# integratedBertha.net
KiCad netlist of a schematic drawn in EAGLE
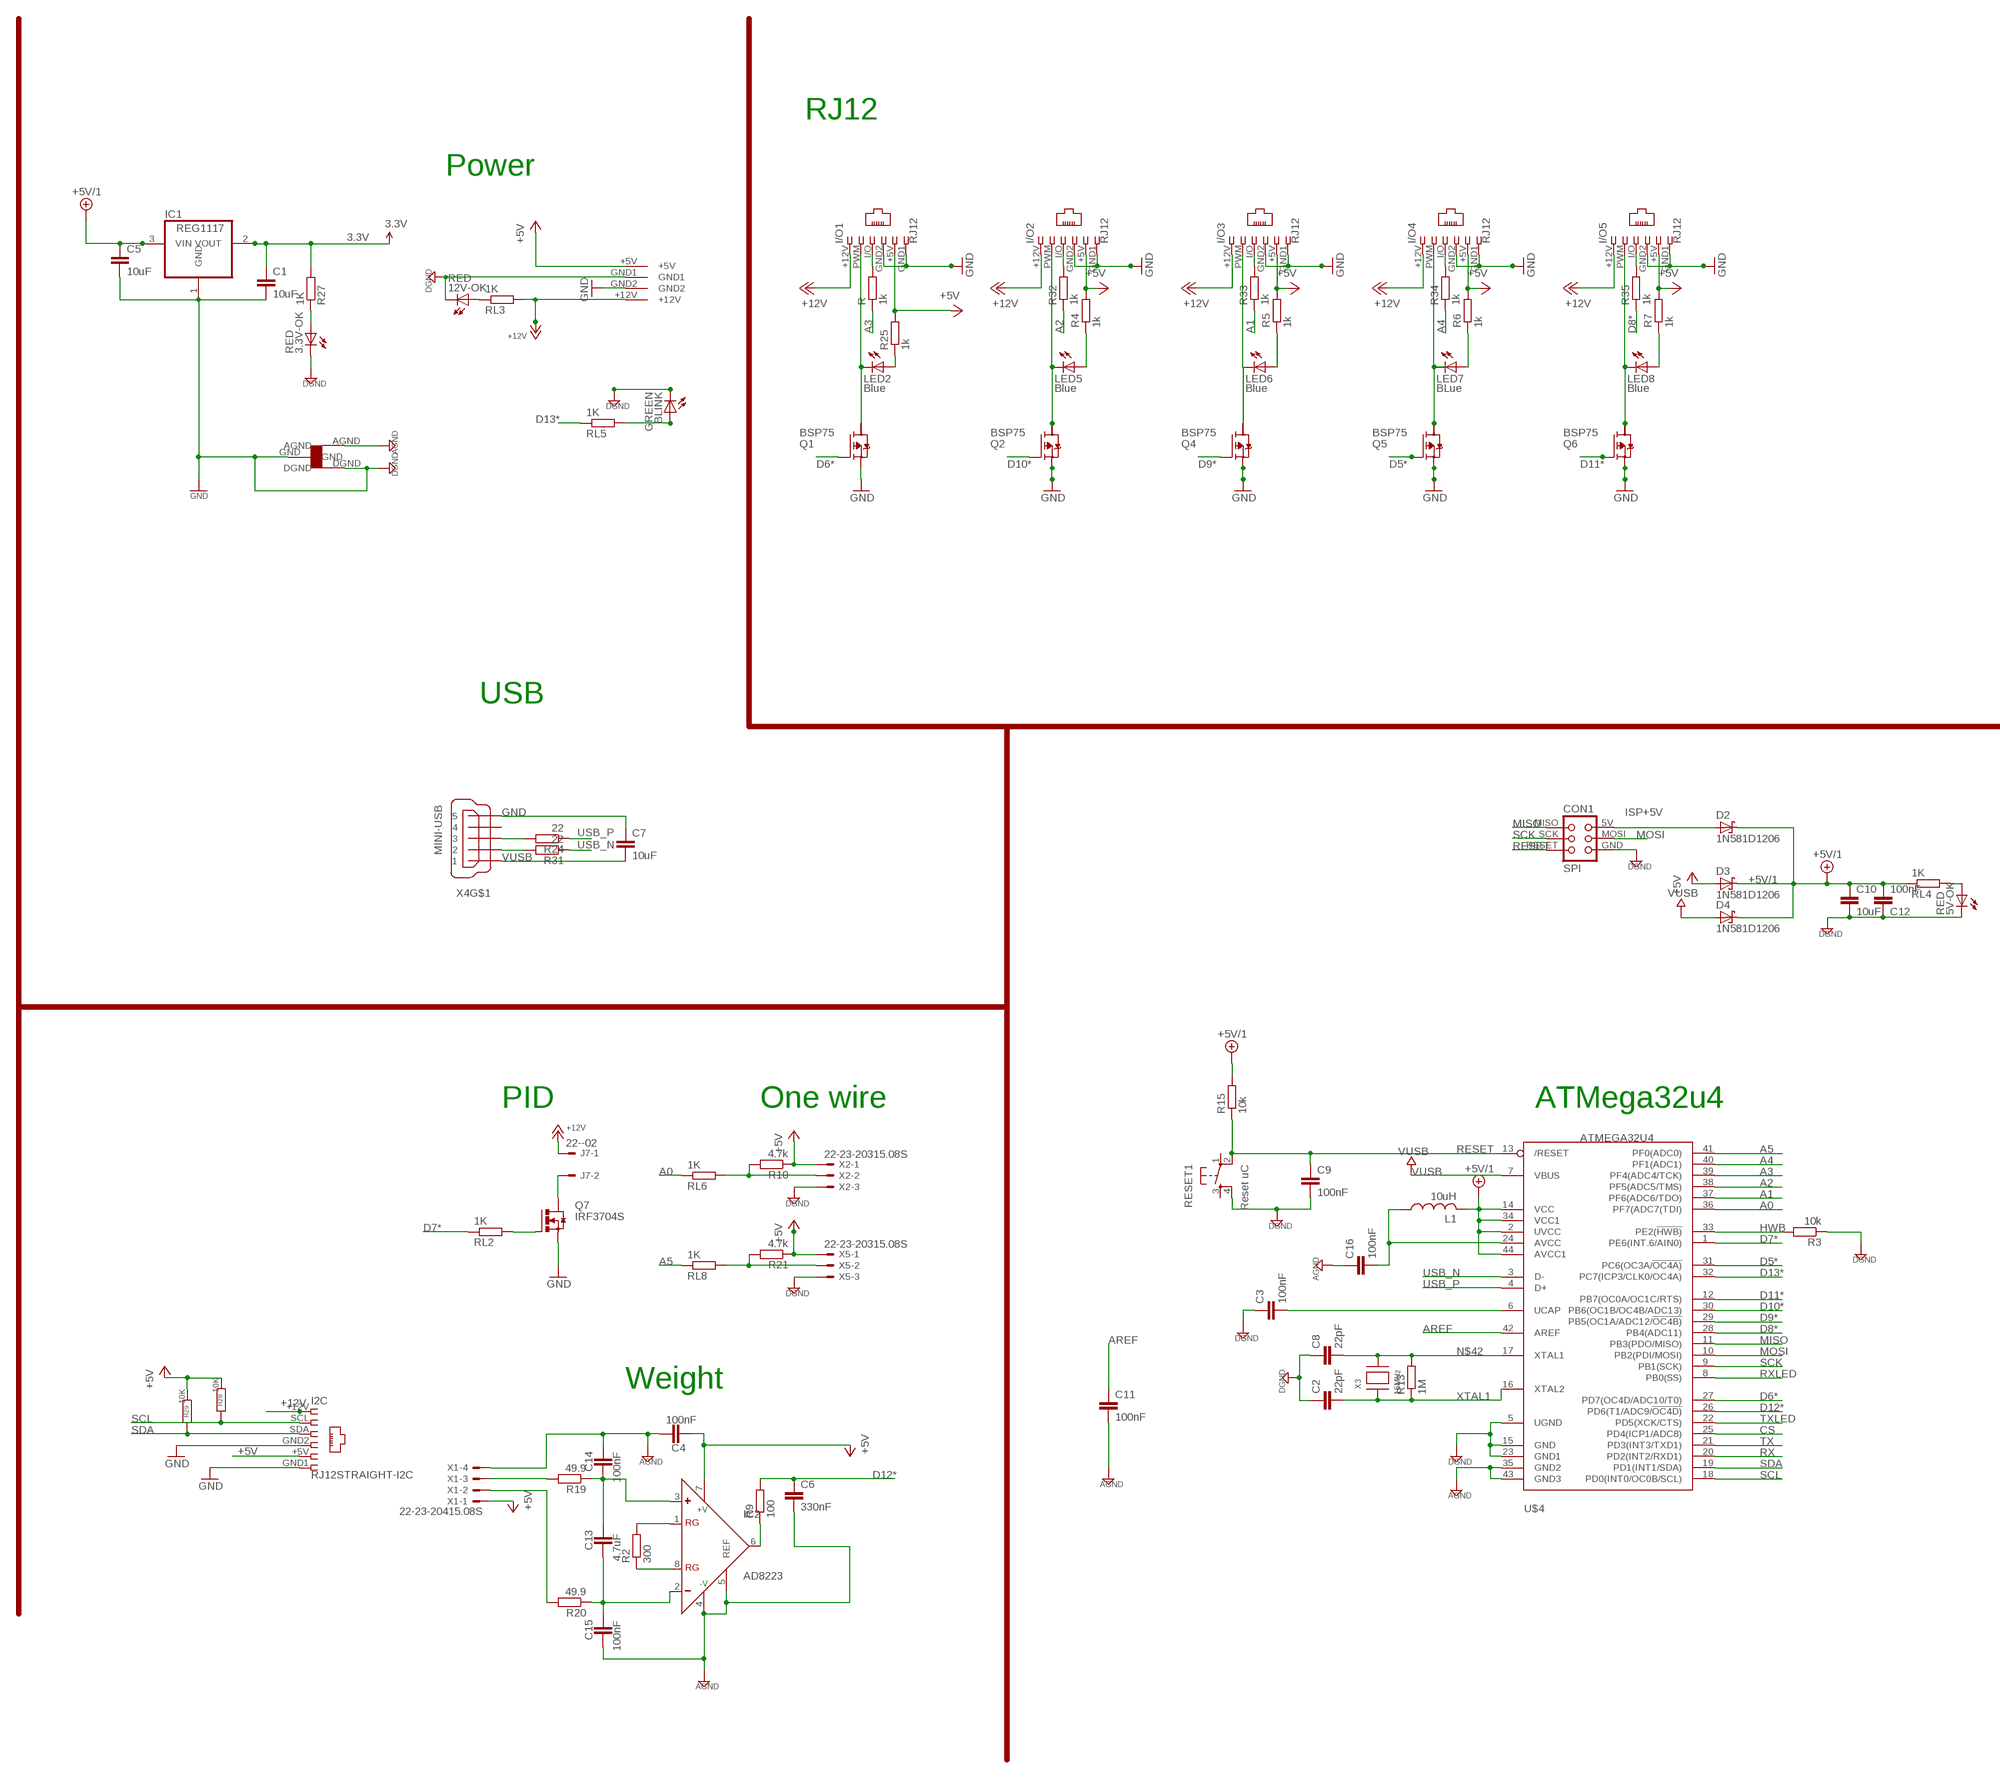
[diagram p0: schematic, sheet 1, part 1 of 2]
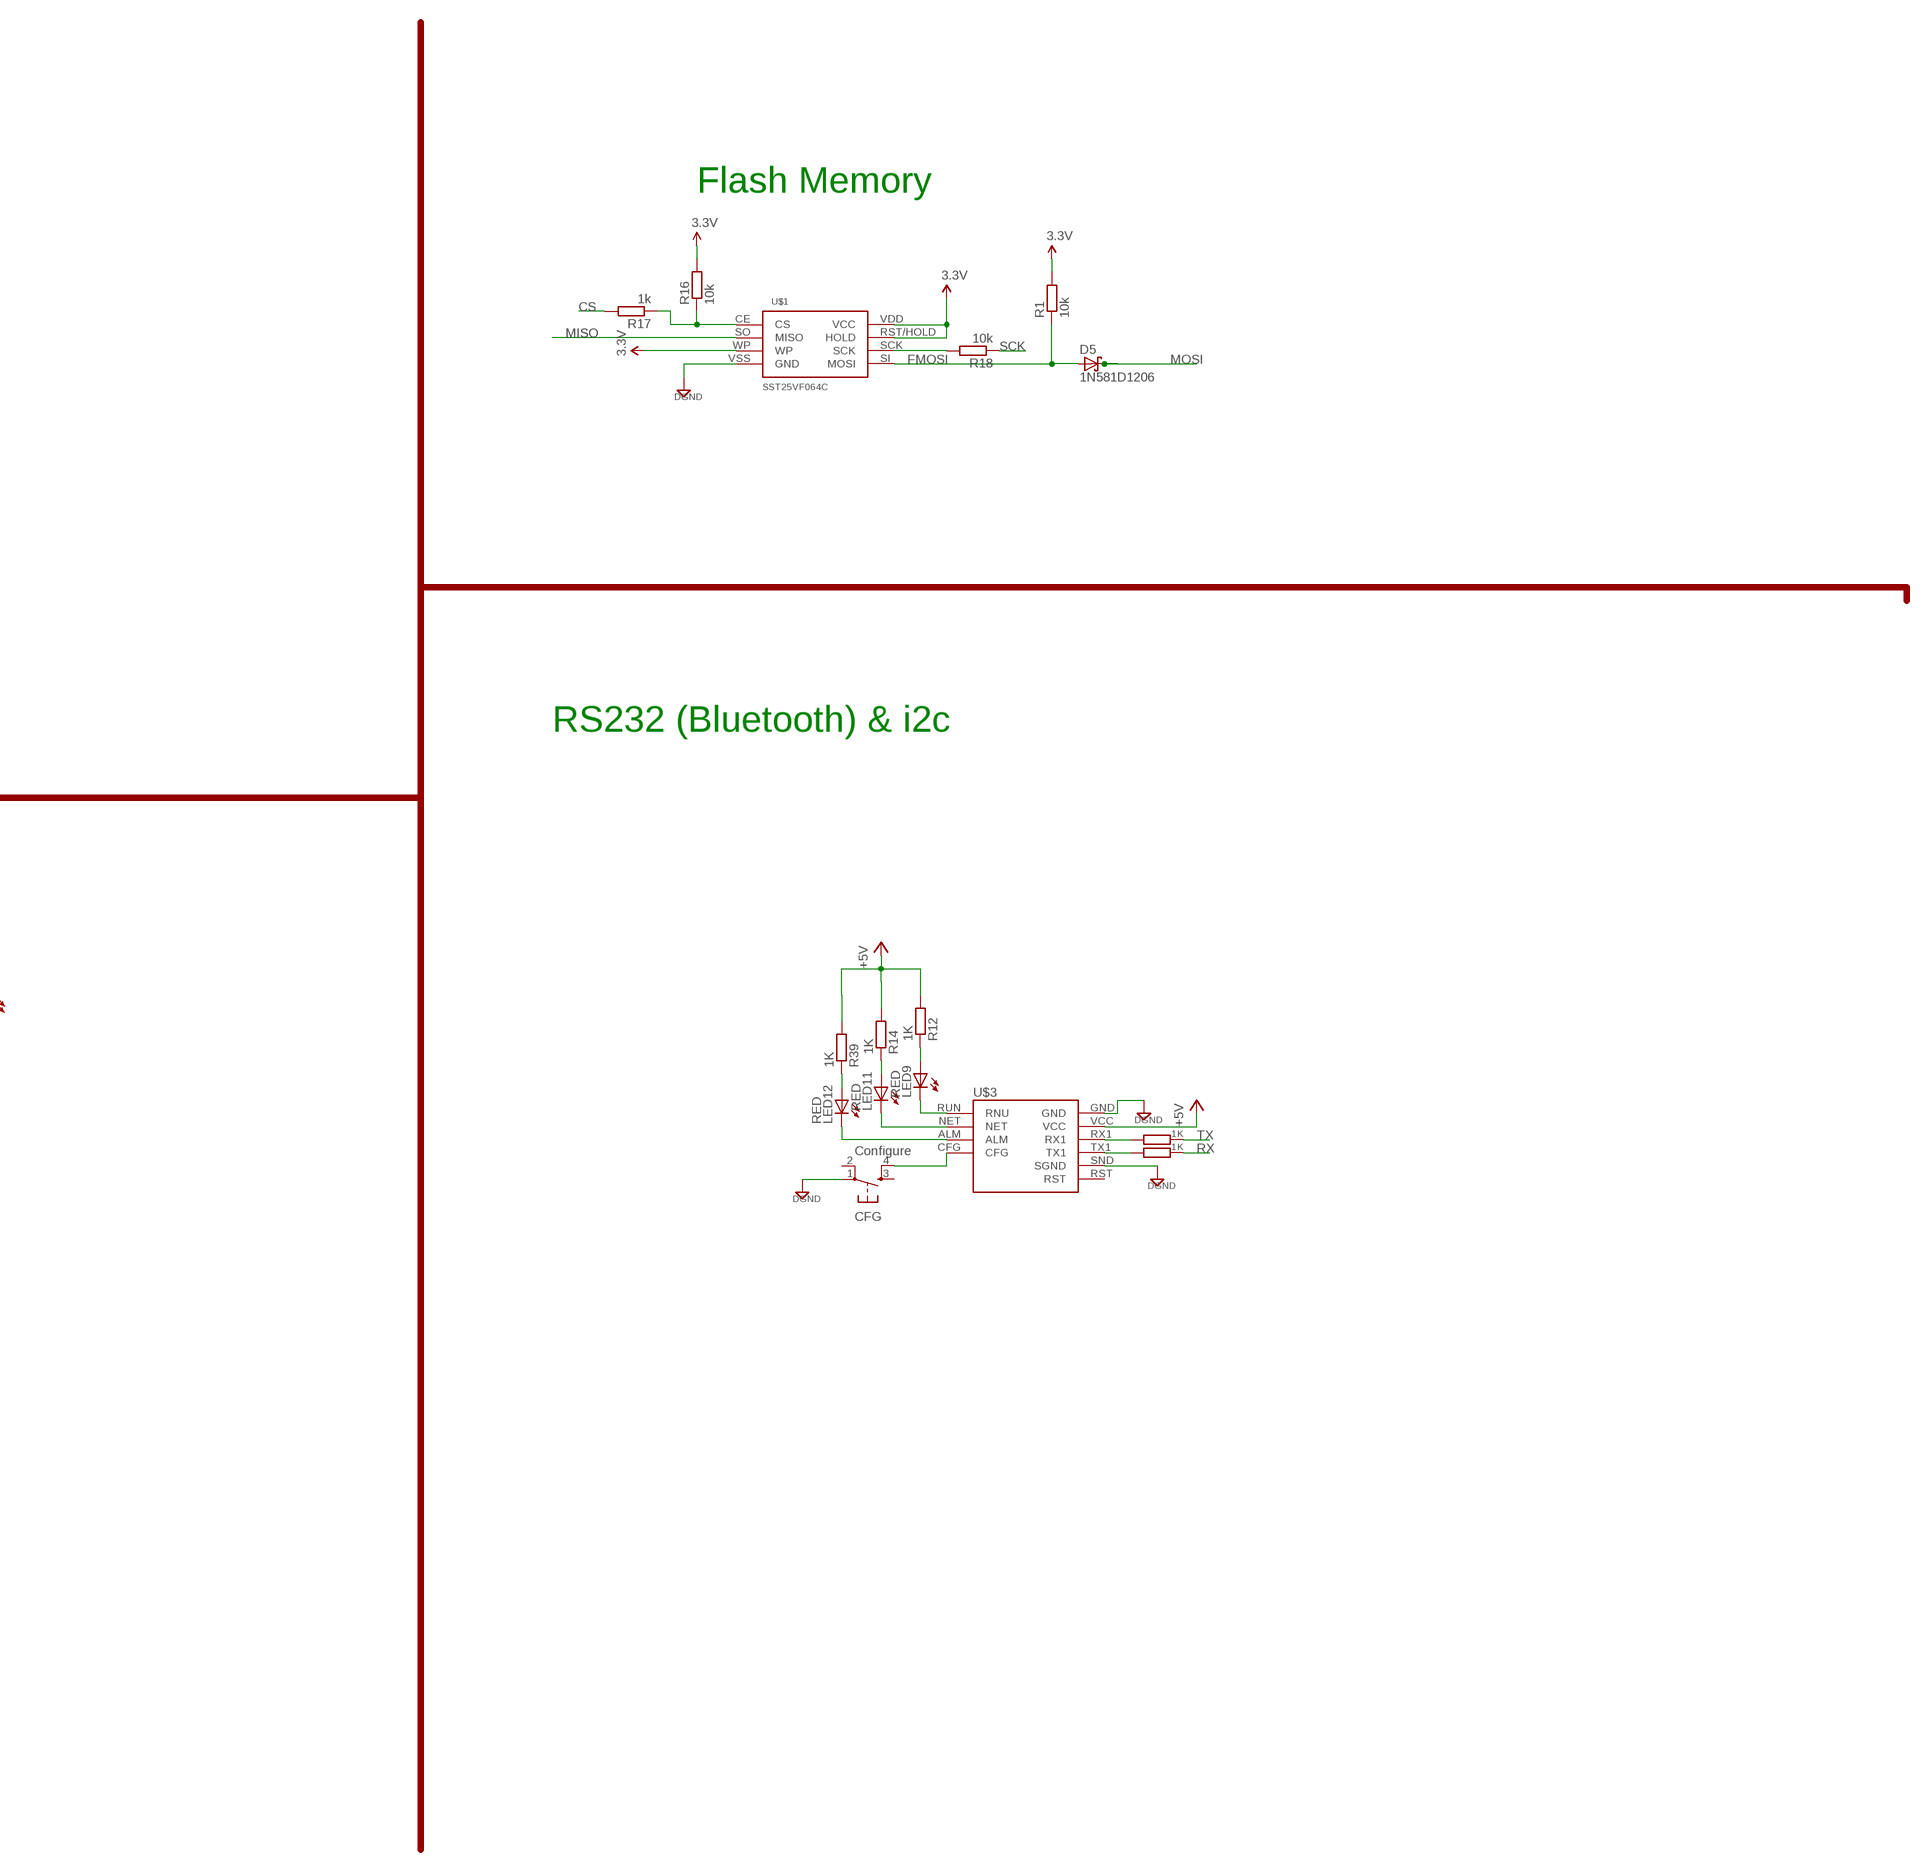
[diagram p1: schematic, sheet 1, part 2 of 2]

(export (version "E")
  (design (tool "Eeschema 10.0.6"))
  (components
    (comp (ref "3.3V-OK")
      (value "RED")
      (footprint "eagle-import:CHIPLED_1206")
      (libsource (lib "eagle-import") (part "LEDCHIPLED_1206"))
    )
    (comp (ref "5V-OK")
      (value "RED")
      (footprint "eagle-import:CHIPLED_1206")
      (libsource (lib "eagle-import") (part "LEDCHIPLED_1206"))
    )
    (comp (ref "12V-OK")
      (value "RED")
      (footprint "eagle-import:CHIPLED_1206")
      (libsource (lib "eagle-import") (part "LEDCHIPLED_1206"))
    )
    (comp (ref "BLINK")
      (value "GREEN")
      (footprint "eagle-import:CHIPLED_1206")
      (libsource (lib "eagle-import") (part "LEDCHIPLED_1206"))
    )
    (comp (ref "C1")
      (value "10uF")
      (footprint "eagle-import:C1206")
      (libsource (lib "eagle-import") (part "C-EUC1206"))
    )
    (comp (ref "C2")
      (value "22pF")
      (footprint "eagle-import:C1206")
      (libsource (lib "eagle-import") (part "C-EUC1206"))
    )
    (comp (ref "C3")
      (value "100nF")
      (footprint "eagle-import:C1206")
      (libsource (lib "eagle-import") (part "C-EUC1206"))
    )
    (comp (ref "C4")
      (value "100nF")
      (footprint "eagle-import:C1206")
      (libsource (lib "eagle-import") (part "C-EUC1206"))
    )
    (comp (ref "C5")
      (value "10uF")
      (footprint "eagle-import:C1206")
      (libsource (lib "eagle-import") (part "C-EUC1206"))
    )
    (comp (ref "C6")
      (value "330nF")
      (footprint "eagle-import:C1206")
      (libsource (lib "eagle-import") (part "C-EUC1206"))
    )
    (comp (ref "C7")
      (value "10uF")
      (footprint "eagle-import:C1206")
      (libsource (lib "eagle-import") (part "C-EUC1206"))
    )
    (comp (ref "C8")
      (value "22pF")
      (footprint "eagle-import:C1206")
      (libsource (lib "eagle-import") (part "C-EUC1206"))
    )
    (comp (ref "C9")
      (value "100nF")
      (footprint "eagle-import:C1206")
      (libsource (lib "eagle-import") (part "C-EUC1206"))
    )
    (comp (ref "C10")
      (value "10uF")
      (footprint "eagle-import:C1206")
      (libsource (lib "eagle-import") (part "C-EUC1206"))
    )
    (comp (ref "C11")
      (value "100nF")
      (footprint "eagle-import:C1206")
      (libsource (lib "eagle-import") (part "C-EUC1206"))
    )
    (comp (ref "C12")
      (value "100nF")
      (footprint "eagle-import:C1206")
      (libsource (lib "eagle-import") (part "C-EUC1206"))
    )
    (comp (ref "C13")
      (value "4.7uF")
      (footprint "eagle-import:C1206")
      (libsource (lib "eagle-import") (part "C-EUC1206"))
    )
    (comp (ref "C14")
      (value "100nF")
      (footprint "eagle-import:C1206")
      (libsource (lib "eagle-import") (part "C-EUC1206"))
    )
    (comp (ref "C15")
      (value "100nF")
      (footprint "eagle-import:C1206")
      (libsource (lib "eagle-import") (part "C-EUC1206"))
    )
    (comp (ref "C16")
      (value "100nF")
      (footprint "eagle-import:C1206")
      (libsource (lib "eagle-import") (part "C-EUC1206"))
    )
    (comp (ref "CFG")
      (value "Configure")
      (footprint "eagle-import:TACTILE_SWITCH_SMD")
      (libsource (lib "eagle-import") (part "TAC_SWITCHSMD"))
    )
    (comp (ref "CON1")
      (value "SPI")
      (footprint "eagle-import:TC2030-MCP-NL")
      (libsource (lib "eagle-import") (part "TINYISPT"))
    )
    (comp (ref "D2")
      (value "1N581D1206")
      (footprint "eagle-import:LED-1206")
      (libsource (lib "eagle-import") (part "1N581D1206"))
    )
    (comp (ref "D3")
      (value "1N581D1206")
      (footprint "eagle-import:LED-1206")
      (libsource (lib "eagle-import") (part "1N581D1206"))
    )
    (comp (ref "D4")
      (value "1N581D1206")
      (footprint "eagle-import:LED-1206")
      (libsource (lib "eagle-import") (part "1N581D1206"))
    )
    (comp (ref "D5")
      (value "1N581D1206")
      (footprint "eagle-import:LED-1206")
      (libsource (lib "eagle-import") (part "1N581D1206"))
    )
    (comp (ref "I/O1")
      (value "RJ12")
      (footprint "eagle-import:RJ12-STRAIGHT")
      (libsource (lib "eagle-import") (part "RJ12STRAIGHT"))
    )
    (comp (ref "I/O2")
      (value "RJ12")
      (footprint "eagle-import:RJ12-STRAIGHT")
      (libsource (lib "eagle-import") (part "RJ12STRAIGHT"))
    )
    (comp (ref "I/O3")
      (value "RJ12")
      (footprint "eagle-import:RJ12-STRAIGHT")
      (libsource (lib "eagle-import") (part "RJ12STRAIGHT"))
    )
    (comp (ref "I/O4")
      (value "RJ12")
      (footprint "eagle-import:RJ12-STRAIGHT")
      (libsource (lib "eagle-import") (part "RJ12STRAIGHT"))
    )
    (comp (ref "I/O5")
      (value "RJ12")
      (footprint "eagle-import:RJ12-STRAIGHT")
      (libsource (lib "eagle-import") (part "RJ12STRAIGHT"))
    )
    (comp (ref "I2C")
      (value "RJ12STRAIGHT-I2C")
      (footprint "eagle-import:RJ12-STRAIGHT-I2C")
      (libsource (lib "eagle-import") (part "RJ12STRAIGHT-I2C"))
    )
    (comp (ref "IC1")
      (value "REG1117")
      (footprint "eagle-import:SOT223")
      (libsource (lib "eagle-import") (part "REG1117"))
    )
    (comp (ref "IC2")
      (value "AD8223")
      (footprint "eagle-import:SO8")
      (fields (field (name "MPN") "AD620AR"))
      (libsource (lib "eagle-import") (part "AD620R"))
    )
    (comp (ref "J7")
      (value "22--02")
      (footprint "eagle-import:2-PIN-5.08S")
      (libsource (lib "eagle-import") (part "22-?-02"))
    )
    (comp (ref "L1")
      (value "10uH")
      (footprint "eagle-import:L2012C")
      (libsource (lib "eagle-import") (part "L-USL2012C"))
    )
    (comp (ref "LED2")
      (value "Blue")
      (footprint "eagle-import:CHIPLED_1206")
      (libsource (lib "eagle-import") (part "LEDCHIPLED_1206"))
    )
    (comp (ref "LED5")
      (value "Blue")
      (footprint "eagle-import:CHIPLED_1206")
      (libsource (lib "eagle-import") (part "LEDCHIPLED_1206"))
    )
    (comp (ref "LED6")
      (value "Blue")
      (footprint "eagle-import:CHIPLED_1206")
      (libsource (lib "eagle-import") (part "LEDCHIPLED_1206"))
    )
    (comp (ref "LED7")
      (value "BLue")
      (footprint "eagle-import:CHIPLED_1206")
      (libsource (lib "eagle-import") (part "LEDCHIPLED_1206"))
    )
    (comp (ref "LED8")
      (value "Blue")
      (footprint "eagle-import:CHIPLED_1206")
      (libsource (lib "eagle-import") (part "LEDCHIPLED_1206"))
    )
    (comp (ref "LED9")
      (value "RED")
      (footprint "eagle-import:CHIPLED_1206")
      (libsource (lib "eagle-import") (part "LEDCHIPLED_1206"))
    )
    (comp (ref "LED11")
      (value "RED")
      (footprint "eagle-import:CHIPLED_1206")
      (libsource (lib "eagle-import") (part "LEDCHIPLED_1206"))
    )
    (comp (ref "LED12")
      (value "RED")
      (footprint "eagle-import:CHIPLED_1206")
      (libsource (lib "eagle-import") (part "LEDCHIPLED_1206"))
    )
    (comp (ref "Q1")
      (value "BSP75")
      (footprint "eagle-import:PG-SOT-223")
      (libsource (lib "eagle-import") (part "BSP613P"))
    )
    (comp (ref "Q2")
      (value "BSP75")
      (footprint "eagle-import:PG-SOT-223")
      (libsource (lib "eagle-import") (part "BSP613P"))
    )
    (comp (ref "Q4")
      (value "BSP75")
      (footprint "eagle-import:PG-SOT-223")
      (libsource (lib "eagle-import") (part "BSP613P"))
    )
    (comp (ref "Q5")
      (value "BSP75")
      (footprint "eagle-import:PG-SOT-223")
      (libsource (lib "eagle-import") (part "BSP613P"))
    )
    (comp (ref "Q6")
      (value "BSP75")
      (footprint "eagle-import:PG-SOT-223")
      (libsource (lib "eagle-import") (part "BSP613P"))
    )
    (comp (ref "Q7")
      (value "IRF3704S")
      (footprint "eagle-import:D2PACK")
      (libsource (lib "eagle-import") (part "IRF3704S"))
    )
    (comp (ref "R")
      (value "1k")
      (footprint "eagle-import:R0805")
      (libsource (lib "eagle-import") (part "R-EU_R0805"))
    )
    (comp (ref "R1")
      (value "10k")
      (footprint "eagle-import:R0805")
      (libsource (lib "eagle-import") (part "R-EU_R0805"))
    )
    (comp (ref "R2")
      (value "300")
      (footprint "eagle-import:R1206")
      (libsource (lib "eagle-import") (part "resistor_R-EU_R1206"))
    )
    (comp (ref "R3")
      (value "10k")
      (footprint "eagle-import:M0805")
      (libsource (lib "eagle-import") (part "resistor_R-EU_M0805"))
    )
    (comp (ref "R4")
      (value "1k")
      (footprint "eagle-import:R0805")
      (libsource (lib "eagle-import") (part "R-EU_R0805"))
    )
    (comp (ref "R5")
      (value "1k")
      (footprint "eagle-import:R0805")
      (libsource (lib "eagle-import") (part "R-EU_R0805"))
    )
    (comp (ref "R6")
      (value "1k")
      (footprint "eagle-import:R0805")
      (libsource (lib "eagle-import") (part "R-EU_R0805"))
    )
    (comp (ref "R7")
      (value "1k")
      (footprint "eagle-import:R0805")
      (libsource (lib "eagle-import") (part "R-EU_R0805"))
    )
    (comp (ref "R8")
      (value "1K")
      (footprint "eagle-import:R0805")
      (libsource (lib "eagle-import") (part "R-EU_R0805"))
    )
    (comp (ref "R9")
      (value "100")
      (footprint "eagle-import:R1206")
      (libsource (lib "eagle-import") (part "resistor_R-EU_R1206"))
    )
    (comp (ref "R10")
      (value "4.7k")
      (footprint "eagle-import:R1206")
      (libsource (lib "eagle-import") (part "resistor_R-EU_R1206"))
    )
    (comp (ref "R11")
      (value "1K")
      (footprint "eagle-import:R0805")
      (libsource (lib "eagle-import") (part "R-EU_R0805"))
    )
    (comp (ref "R12")
      (value "1K")
      (footprint "eagle-import:R0805")
      (libsource (lib "eagle-import") (part "R-EU_R0805"))
    )
    (comp (ref "R13")
      (value "1M")
      (footprint "eagle-import:R1206")
      (libsource (lib "eagle-import") (part "R-EU_R1206"))
    )
    (comp (ref "R14")
      (value "1K")
      (footprint "eagle-import:R0805")
      (libsource (lib "eagle-import") (part "R-EU_R0805"))
    )
    (comp (ref "R15")
      (value "10k")
      (footprint "eagle-import:M0805")
      (libsource (lib "eagle-import") (part "resistor_R-EU_M0805"))
    )
    (comp (ref "R16")
      (value "10k")
      (footprint "eagle-import:R0805")
      (libsource (lib "eagle-import") (part "R-EU_R0805"))
    )
    (comp (ref "R17")
      (value "1k")
      (footprint "eagle-import:R0805")
      (libsource (lib "eagle-import") (part "R-EU_R0805"))
    )
    (comp (ref "R18")
      (value "10k")
      (footprint "eagle-import:R0805")
      (libsource (lib "eagle-import") (part "R-EU_R0805"))
    )
    (comp (ref "R19")
      (value "49.9")
      (footprint "eagle-import:R1206")
      (libsource (lib "eagle-import") (part "resistor_R-EU_R1206"))
    )
    (comp (ref "R20")
      (value "49.9")
      (footprint "eagle-import:R1206")
      (libsource (lib "eagle-import") (part "resistor_R-EU_R1206"))
    )
    (comp (ref "R21")
      (value "4.7k")
      (footprint "eagle-import:R1206")
      (libsource (lib "eagle-import") (part "resistor_R-EU_R1206"))
    )
    (comp (ref "R24")
      (value "22")
      (footprint "eagle-import:M1206")
      (libsource (lib "eagle-import") (part "resistor_R-EU_M1206"))
    )
    (comp (ref "R25")
      (value "1k")
      (footprint "eagle-import:R0805")
      (libsource (lib "eagle-import") (part "R-EU_R0805"))
    )
    (comp (ref "R27")
      (value "1K")
      (footprint "eagle-import:R0805")
      (libsource (lib "eagle-import") (part "R-EU_R0805"))
    )
    (comp (ref "R28")
      (value "10K")
      (footprint "eagle-import:M0805")
      (libsource (lib "eagle-import") (part "resistor_R-EU_M0805"))
    )
    (comp (ref "R29")
      (value "10K")
      (footprint "eagle-import:M0805")
      (libsource (lib "eagle-import") (part "resistor_R-EU_M0805"))
    )
    (comp (ref "R31")
      (value "22")
      (footprint "eagle-import:M1206")
      (libsource (lib "eagle-import") (part "resistor_R-EU_M1206"))
    )
    (comp (ref "R32")
      (value "1k")
      (footprint "eagle-import:R0805")
      (libsource (lib "eagle-import") (part "R-EU_R0805"))
    )
    (comp (ref "R33")
      (value "1k")
      (footprint "eagle-import:R0805")
      (libsource (lib "eagle-import") (part "R-EU_R0805"))
    )
    (comp (ref "R34")
      (value "1k")
      (footprint "eagle-import:R0805")
      (libsource (lib "eagle-import") (part "R-EU_R0805"))
    )
    (comp (ref "R35")
      (value "1k")
      (footprint "eagle-import:R0805")
      (libsource (lib "eagle-import") (part "R-EU_R0805"))
    )
    (comp (ref "R39")
      (value "1K")
      (footprint "eagle-import:R0805")
      (libsource (lib "eagle-import") (part "R-EU_R0805"))
    )
    (comp (ref "RESET1")
      (value "Reset uC")
      (footprint "eagle-import:TACTILE_SWITCH_SMD")
      (libsource (lib "eagle-import") (part "TAC_SWITCHSMD"))
    )
    (comp (ref "RL2")
      (value "1K")
      (footprint "eagle-import:R0805")
      (libsource (lib "eagle-import") (part "R-EU_R0805"))
    )
    (comp (ref "RL3")
      (value "1K")
      (footprint "eagle-import:R0805")
      (libsource (lib "eagle-import") (part "R-EU_R0805"))
    )
    (comp (ref "RL4")
      (value "1K")
      (footprint "eagle-import:R0805")
      (libsource (lib "eagle-import") (part "resistor_R-EU_R0805"))
    )
    (comp (ref "RL5")
      (value "1K")
      (footprint "eagle-import:R0805")
      (libsource (lib "eagle-import") (part "R-EU_R0805"))
    )
    (comp (ref "RL6")
      (value "1K")
      (footprint "eagle-import:R0805")
      (libsource (lib "eagle-import") (part "R-EU_R0805"))
    )
    (comp (ref "RL8")
      (value "1K")
      (footprint "eagle-import:R0805")
      (libsource (lib "eagle-import") (part "R-EU_R0805"))
    )
    (comp (ref "U$1")
      (value "SST25VF064C")
      (footprint "eagle-import:SOIC_8-LEAD")
      (libsource (lib "eagle-import") (part "SST25VF064C"))
    )
    (comp (ref "U$2")
      (value "STARGND")
      (footprint "eagle-import:STAR")
      (libsource (lib "eagle-import") (part "STARGND"))
    )
    (comp (ref "U$3")
      (value "SZ05-ZIGBEE")
      (footprint "eagle-import:SZ05-ZIGBEE4")
      (libsource (lib "eagle-import") (part "SZ05-ZIGBEETHROUGHHOLE"))
    )
    (comp (ref "U$4")
      (value "ATMEGA32U4")
      (footprint "eagle-import:TQFP44")
      (libsource (lib "eagle-import") (part "ATMEGA32U4-AU"))
    )
    (comp (ref "U$6")
      (value "KPJX-4S-S")
      (footprint "eagle-import:KPJX-4S-S")
      (libsource (lib "eagle-import") (part "KPJX-4S-S"))
    )
    (comp (ref "X1")
      (value "22-23-20415.08S")
      (footprint "eagle-import:4-PIN-5.08S")
      (libsource (lib "eagle-import") (part "22-23-20415.08S"))
    )
    (comp (ref "X2")
      (value "22-23-20315.08S")
      (footprint "eagle-import:3-PIN-5.08S")
      (libsource (lib "eagle-import") (part "22-23-20315.08S"))
    )
    (comp (ref "X3")
      (value "16MHz")
      (footprint "eagle-import:NX6035")
      (libsource (lib "eagle-import") (part "XTALNX6035"))
    )
    (comp (ref "X4")
      (value "MINI-USB")
      (footprint "eagle-import:32005-201")
      (libsource (lib "eagle-import") (part "MINI-USB-SCHIELD-32005-201"))
    )
    (comp (ref "X5")
      (value "22-23-20315.08S")
      (footprint "eagle-import:3-PIN-5.08S")
      (libsource (lib "eagle-import") (part "22-23-20315.08S"))
    )
  )
  (nets
    (net (code "1") (name "+5V") (class "Default")
      (node (ref "C4") (pin "2") (pinfunction "2_2") (pintype "passive"))
      (node (ref "D3") (pin "A") (pinfunction "A_A") (pintype "passive"))
      (node (ref "I/O1") (pin "+5V") (pinfunction "5_+5V") (pintype "bidirectional"))
      (node (ref "I/O2") (pin "+5V") (pinfunction "5_+5V") (pintype "bidirectional"))
      (node (ref "I/O3") (pin "+5V") (pinfunction "5_+5V") (pintype "bidirectional"))
      (node (ref "I/O4") (pin "+5V") (pinfunction "5_+5V") (pintype "bidirectional"))
      (node (ref "I/O5") (pin "+5V") (pinfunction "5_+5V") (pintype "bidirectional"))
      (node (ref "I2C") (pin "+5V") (pinfunction "5_+5V") (pintype "bidirectional"))
      (node (ref "IC2") (pin "7") (pinfunction "+V_7") (pintype "power_in"))
      (node (ref "R10") (pin "1") (pinfunction "1_1") (pintype "passive"))
      (node (ref "R12") (pin "2") (pinfunction "2_2") (pintype "passive"))
      (node (ref "R14") (pin "2") (pinfunction "2_2") (pintype "passive"))
      (node (ref "R21") (pin "1") (pinfunction "1_1") (pintype "passive"))
      (node (ref "R25") (pin "2") (pinfunction "2_2") (pintype "passive"))
      (node (ref "R28") (pin "1") (pinfunction "1_1") (pintype "passive"))
      (node (ref "R29") (pin "1") (pinfunction "1_1") (pintype "passive"))
      (node (ref "R39") (pin "2") (pinfunction "2_2") (pintype "passive"))
      (node (ref "R4") (pin "2") (pinfunction "2_2") (pintype "passive"))
      (node (ref "R5") (pin "2") (pinfunction "2_2") (pintype "passive"))
      (node (ref "R6") (pin "2") (pinfunction "2_2") (pintype "passive"))
      (node (ref "R7") (pin "2") (pinfunction "2_2") (pintype "passive"))
      (node (ref "U$3") (pin "VCC") (pinfunction "VCC_VCC") (pintype "bidirectional"))
      (node (ref "U$6") (pin "+5V") (pinfunction "+5V_+5V") (pintype "power_in"))
      (node (ref "X1") (pin "1") (pinfunction "S_1") (pintype "passive"))
      (node (ref "X2") (pin "1") (pinfunction "S_1") (pintype "passive"))
      (node (ref "X5") (pin "1") (pinfunction "S_1") (pintype "passive"))
    )
    (net (code "2") (name "+5V{slash}1") (class "Default")
      (node (ref "C10") (pin "1") (pinfunction "1_1") (pintype "passive"))
      (node (ref "C12") (pin "2") (pinfunction "2_2") (pintype "passive"))
      (node (ref "C5") (pin "1") (pinfunction "1_1") (pintype "passive"))
      (node (ref "D2") (pin "C") (pinfunction "C_C") (pintype "passive"))
      (node (ref "D3") (pin "C") (pinfunction "C_C") (pintype "passive"))
      (node (ref "D4") (pin "C") (pinfunction "C_C") (pintype "passive"))
      (node (ref "IC1") (pin "3") (pinfunction "VIN_3") (pintype "input"))
      (node (ref "L1") (pin "2") (pinfunction "2_2") (pintype "passive"))
      (node (ref "R15") (pin "2") (pinfunction "2_2") (pintype "passive"))
      (node (ref "RL4") (pin "1") (pinfunction "1_1") (pintype "passive"))
      (node (ref "U$4") (pin "14") (pinfunction "VCC_14") (pintype "bidirectional"))
      (node (ref "U$4") (pin "2") (pinfunction "UVCC_2") (pintype "bidirectional"))
      (node (ref "U$4") (pin "34") (pinfunction "VCC1_34") (pintype "bidirectional"))
      (node (ref "U$4") (pin "44") (pinfunction "AVCC1_44") (pintype "bidirectional"))
    )
    (net (code "3") (name "+12V") (class "Default")
      (node (ref "I/O1") (pin "+12V") (pinfunction "1_+12V") (pintype "bidirectional"))
      (node (ref "I/O2") (pin "+12V") (pinfunction "1_+12V") (pintype "bidirectional"))
      (node (ref "I/O3") (pin "+12V") (pinfunction "1_+12V") (pintype "bidirectional"))
      (node (ref "I/O4") (pin "+12V") (pinfunction "1_+12V") (pintype "bidirectional"))
      (node (ref "I/O5") (pin "+12V") (pinfunction "1_+12V") (pintype "bidirectional"))
      (node (ref "I2C") (pin "+12V") (pinfunction "1_+12V") (pintype "bidirectional"))
      (node (ref "J7") (pin "1") (pinfunction "S_1") (pintype "passive"))
      (node (ref "RL3") (pin "2") (pinfunction "2_2") (pintype "passive"))
      (node (ref "U$6") (pin "+12V") (pinfunction "+12V_+12V") (pintype "power_in"))
    )
    (net (code "4") (name "/A0") (class "Default")
      (node (ref "RL6") (pin "1") (pinfunction "1_1") (pintype "passive"))
      (node (ref "U$4") (pin "36") (pinfunction "PF7(ADC7(TDI)_36") (pintype "bidirectional"))
    )
    (net (code "5") (name "/A1") (class "Default")
      (node (ref "R33") (pin "1") (pinfunction "1_1") (pintype "passive"))
      (node (ref "U$4") (pin "37") (pinfunction "PF6(ADC6/TDO)_37") (pintype "bidirectional"))
    )
    (net (code "6") (name "/A2") (class "Default")
      (node (ref "R32") (pin "1") (pinfunction "1_1") (pintype "passive"))
      (node (ref "U$4") (pin "38") (pinfunction "PF5(ADC5/TMS)_38") (pintype "bidirectional"))
    )
    (net (code "7") (name "/A3") (class "Default")
      (node (ref "R") (pin "1") (pinfunction "1_1") (pintype "passive"))
      (node (ref "U$4") (pin "39") (pinfunction "PF4(ADC4/TCK)_39") (pintype "bidirectional"))
    )
    (net (code "8") (name "/A4") (class "Default")
      (node (ref "R34") (pin "1") (pinfunction "1_1") (pintype "passive"))
      (node (ref "U$4") (pin "40") (pinfunction "PF1(ADC1)_40") (pintype "bidirectional"))
    )
    (net (code "9") (name "/A5") (class "Default")
      (node (ref "RL8") (pin "1") (pinfunction "1_1") (pintype "passive"))
      (node (ref "U$4") (pin "41") (pinfunction "PF0(ADC0)_41") (pintype "bidirectional"))
    )
    (net (code "10") (name "/AREF") (class "Default")
      (node (ref "C11") (pin "1") (pinfunction "1_1") (pintype "passive"))
      (node (ref "U$4") (pin "42") (pinfunction "AREF_42") (pintype "bidirectional"))
    )
    (net (code "11") (name "/CS") (class "Default")
      (node (ref "R17") (pin "2") (pinfunction "2_2") (pintype "passive"))
      (node (ref "U$4") (pin "25") (pinfunction "PD4(ICP1/ADC8)_25") (pintype "bidirectional"))
    )
    (net (code "12") (name "/D5*") (class "Default")
      (node (ref "Q5") (pin "1") (pinfunction "G_1") (pintype "passive"))
      (node (ref "U$4") (pin "31") (pinfunction "PC6(OC3A/~{OC4A})_31") (pintype "bidirectional"))
    )
    (net (code "13") (name "/D6*") (class "Default")
      (node (ref "Q1") (pin "1") (pinfunction "G_1") (pintype "passive"))
      (node (ref "U$4") (pin "27") (pinfunction "PD7(OC4D/ADC10/T0)_27") (pintype "bidirectional"))
    )
    (net (code "14") (name "/D7*") (class "Default")
      (node (ref "RL2") (pin "1") (pinfunction "1_1") (pintype "passive"))
      (node (ref "U$4") (pin "1") (pinfunction "PE6(INT.6/AIN0)_1") (pintype "bidirectional"))
    )
    (net (code "15") (name "/D8*") (class "Default")
      (node (ref "R35") (pin "1") (pinfunction "1_1") (pintype "passive"))
      (node (ref "U$4") (pin "28") (pinfunction "PB4(ADC11)_28") (pintype "bidirectional"))
    )
    (net (code "16") (name "/D9*") (class "Default")
      (node (ref "Q4") (pin "1") (pinfunction "G_1") (pintype "passive"))
      (node (ref "U$4") (pin "29") (pinfunction "PB5(OC1A/ADC12/~{OC4B})_29") (pintype "bidirectional"))
    )
    (net (code "17") (name "/D10*") (class "Default")
      (node (ref "Q2") (pin "1") (pinfunction "G_1") (pintype "passive"))
      (node (ref "U$4") (pin "30") (pinfunction "PB6(OC1B/OC4B/ADC13)_30") (pintype "bidirectional"))
    )
    (net (code "18") (name "/D11*") (class "Default")
      (node (ref "Q6") (pin "1") (pinfunction "G_1") (pintype "passive"))
      (node (ref "U$4") (pin "12") (pinfunction "PB7(OC0A/OC1C/RTS)_12") (pintype "bidirectional"))
    )
    (net (code "19") (name "/D12*") (class "Default")
      (node (ref "C6") (pin "1") (pinfunction "1_1") (pintype "passive"))
      (node (ref "R9") (pin "2") (pinfunction "2_2") (pintype "passive"))
      (node (ref "U$4") (pin "26") (pinfunction "PD6(T1/ADC9/~{OC4D})_26") (pintype "bidirectional"))
    )
    (net (code "20") (name "/D13*") (class "Default")
      (node (ref "RL5") (pin "1") (pinfunction "1_1") (pintype "passive"))
      (node (ref "U$4") (pin "32") (pinfunction "PC7(ICP3/CLK0/OC4A)_32") (pintype "bidirectional"))
    )
    (net (code "21") (name "/FMOSI") (class "Default")
      (node (ref "D5") (pin "A") (pinfunction "A_A") (pintype "passive"))
      (node (ref "R1") (pin "1") (pinfunction "1_1") (pintype "passive"))
      (node (ref "U$1") (pin "SI") (pinfunction "MOSI_SI") (pintype "bidirectional"))
    )
    (net (code "22") (name "/HWB") (class "Default")
      (node (ref "R3") (pin "2") (pinfunction "2_2") (pintype "passive"))
      (node (ref "U$4") (pin "33") (pinfunction "PE2(~{HWB})_33") (pintype "bidirectional"))
    )
    (net (code "23") (name "/ISP+5V") (class "Default")
      (node (ref "CON1") (pin "5V") (pinfunction "VCC_5V") (pintype "passive"))
      (node (ref "D2") (pin "A") (pinfunction "A_A") (pintype "passive"))
    )
    (net (code "24") (name "/MISO") (class "Default")
      (node (ref "CON1") (pin "MISO") (pinfunction "MISO_MISO") (pintype "passive"))
      (node (ref "U$1") (pin "SO") (pinfunction "MISO_SO") (pintype "bidirectional"))
      (node (ref "U$4") (pin "11") (pinfunction "PB3(PDO/MISO)_11") (pintype "bidirectional"))
    )
    (net (code "25") (name "/MOSI") (class "Default")
      (node (ref "CON1") (pin "MOSI") (pinfunction "MOSI_MOSI") (pintype "passive"))
      (node (ref "D5") (pin "C") (pinfunction "C_C") (pintype "passive"))
      (node (ref "U$4") (pin "10") (pinfunction "PB2(PDI/MOSI)_10") (pintype "bidirectional"))
    )
    (net (code "26") (name "/N$42") (class "Default")
      (node (ref "C8") (pin "2") (pinfunction "2_2") (pintype "passive"))
      (node (ref "R13") (pin "2") (pinfunction "2_2") (pintype "passive"))
      (node (ref "U$4") (pin "17") (pinfunction "XTAL1_17") (pintype "bidirectional"))
      (node (ref "X3") (pin "P$2") (pinfunction "P$2_P$2") (pintype "bidirectional"))
    )
    (net (code "27") (name "/RESET") (class "Default")
      (node (ref "C9") (pin "1") (pinfunction "1_1") (pintype "passive"))
      (node (ref "CON1") (pin "RESET") (pinfunction "RESET_RESET") (pintype "passive"))
      (node (ref "R15") (pin "1") (pinfunction "1_1") (pintype "passive"))
      (node (ref "RESET1") (pin "2") (pinfunction "2_2") (pintype "passive"))
      (node (ref "U$4") (pin "13") (pinfunction "/RESET_13") (pintype "bidirectional"))
    )
    (net (code "28") (name "/RX") (class "Default")
      (node (ref "R8") (pin "1") (pinfunction "1_1") (pintype "passive"))
      (node (ref "U$4") (pin "20") (pinfunction "PD2(INT2/RXD1)_20") (pintype "bidirectional"))
    )
    (net (code "29") (name "/RXLED") (class "Default")
      (node (ref "U$4") (pin "8") (pinfunction "PB0(SS)_8") (pintype "bidirectional"))
    )
    (net (code "30") (name "/SCK") (class "Default")
      (node (ref "CON1") (pin "SCK") (pinfunction "SCK_SCK") (pintype "passive"))
      (node (ref "R18") (pin "1") (pinfunction "1_1") (pintype "passive"))
      (node (ref "U$4") (pin "9") (pinfunction "PB1(SCK)_9") (pintype "bidirectional"))
    )
    (net (code "31") (name "/SCL") (class "Default")
      (node (ref "I2C") (pin "SCL") (pinfunction "2_SCL") (pintype "bidirectional"))
      (node (ref "R28") (pin "2") (pinfunction "2_2") (pintype "passive"))
      (node (ref "U$4") (pin "18") (pinfunction "PD0(INT0/OC0B/SCL)_18") (pintype "bidirectional"))
    )
    (net (code "32") (name "/SDA") (class "Default")
      (node (ref "I2C") (pin "SDA") (pinfunction "3_SDA") (pintype "bidirectional"))
      (node (ref "R29") (pin "2") (pinfunction "2_2") (pintype "passive"))
      (node (ref "U$4") (pin "19") (pinfunction "PD1(INT1/SDA)_19") (pintype "bidirectional"))
    )
    (net (code "33") (name "/TX") (class "Default")
      (node (ref "R11") (pin "1") (pinfunction "1_1") (pintype "passive"))
      (node (ref "U$4") (pin "21") (pinfunction "PD3(INT3/TXD1)_21") (pintype "bidirectional"))
    )
    (net (code "34") (name "/TXLED") (class "Default")
      (node (ref "U$4") (pin "22") (pinfunction "PD5(XCK/CTS)_22") (pintype "bidirectional"))
    )
    (net (code "35") (name "/USB_N") (class "Default")
      (node (ref "R31") (pin "1") (pinfunction "1_1") (pintype "passive"))
      (node (ref "U$4") (pin "3") (pinfunction "D-_3") (pintype "bidirectional"))
    )
    (net (code "36") (name "/USB_P") (class "Default")
      (node (ref "R24") (pin "1") (pinfunction "1_1") (pintype "passive"))
      (node (ref "U$4") (pin "4") (pinfunction "D+_4") (pintype "bidirectional"))
    )
    (net (code "37") (name "/XTAL1") (class "Default")
      (node (ref "C2") (pin "2") (pinfunction "2_2") (pintype "passive"))
      (node (ref "R13") (pin "1") (pinfunction "1_1") (pintype "passive"))
      (node (ref "U$4") (pin "16") (pinfunction "XTAL2_16") (pintype "bidirectional"))
      (node (ref "X3") (pin "P$1") (pinfunction "P$1_P$1") (pintype "bidirectional"))
    )
    (net (code "38") (name "3.3V") (class "Default")
      (node (ref "C1") (pin "1") (pinfunction "1_1") (pintype "passive"))
      (node (ref "IC1") (pin "2") (pinfunction "VOUT_2") (pintype "output"))
      (node (ref "R1") (pin "2") (pinfunction "2_2") (pintype "passive"))
      (node (ref "R16") (pin "2") (pinfunction "2_2") (pintype "passive"))
      (node (ref "R27") (pin "2") (pinfunction "2_2") (pintype "passive"))
      (node (ref "U$1") (pin "RST/HOLD") (pinfunction "HOLD_RST/HOLD") (pintype "bidirectional"))
      (node (ref "U$1") (pin "VDD") (pinfunction "VCC_VDD") (pintype "bidirectional"))
      (node (ref "U$1") (pin "WP") (pinfunction "WP_WP") (pintype "bidirectional"))
    )
    (net (code "39") (name "AGND") (class "Default")
      (node (ref "C11") (pin "2") (pinfunction "2_2") (pintype "passive"))
      (node (ref "C14") (pin "1") (pinfunction "1_1") (pintype "passive"))
      (node (ref "C15") (pin "2") (pinfunction "2_2") (pintype "passive"))
      (node (ref "C16") (pin "1") (pinfunction "1_1") (pintype "passive"))
      (node (ref "C4") (pin "1") (pinfunction "1_1") (pintype "passive"))
      (node (ref "C6") (pin "2") (pinfunction "2_2") (pintype "passive"))
      (node (ref "IC2") (pin "4") (pinfunction "-V_4") (pintype "power_in"))
      (node (ref "IC2") (pin "5") (pinfunction "REF_5") (pintype "passive"))
      (node (ref "U$2") (pin "AGND") (pinfunction "AGND_AGND") (pintype "output"))
      (node (ref "U$4") (pin "35") (pinfunction "GND2_35") (pintype "bidirectional"))
      (node (ref "U$4") (pin "43") (pinfunction "GND3_43") (pintype "bidirectional"))
      (node (ref "X1") (pin "4") (pinfunction "S_4") (pintype "passive"))
    )
    (net (code "40") (name "DGND") (class "Default")
      (node (ref "12V-OK") (pin "C") (pinfunction "C_C") (pintype "passive"))
      (node (ref "3.3V-OK") (pin "C") (pinfunction "C_C") (pintype "passive"))
      (node (ref "5V-OK") (pin "C") (pinfunction "C_C") (pintype "passive"))
      (node (ref "BLINK") (pin "C") (pinfunction "C_C") (pintype "passive"))
      (node (ref "C1") (pin "2") (pinfunction "2_2") (pintype "passive"))
      (node (ref "C10") (pin "2") (pinfunction "2_2") (pintype "passive"))
      (node (ref "C12") (pin "1") (pinfunction "1_1") (pintype "passive"))
      (node (ref "C2") (pin "1") (pinfunction "1_1") (pintype "passive"))
      (node (ref "C3") (pin "1") (pinfunction "1_1") (pintype "passive"))
      (node (ref "C5") (pin "2") (pinfunction "2_2") (pintype "passive"))
      (node (ref "C7") (pin "1") (pinfunction "1_1") (pintype "passive"))
      (node (ref "C8") (pin "1") (pinfunction "1_1") (pintype "passive"))
      (node (ref "C9") (pin "2") (pinfunction "2_2") (pintype "passive"))
      (node (ref "CFG") (pin "1") (pinfunction "1_1") (pintype "passive"))
      (node (ref "CON1") (pin "GND") (pinfunction "GND_GND") (pintype "passive"))
      (node (ref "I/O1") (pin "GND1") (pinfunction "6_GND1") (pintype "bidirectional"))
      (node (ref "I/O1") (pin "GND2") (pinfunction "4_GND2") (pintype "bidirectional"))
      (node (ref "I/O2") (pin "GND1") (pinfunction "6_GND1") (pintype "bidirectional"))
      (node (ref "I/O2") (pin "GND2") (pinfunction "4_GND2") (pintype "bidirectional"))
      (node (ref "I/O3") (pin "GND1") (pinfunction "6_GND1") (pintype "bidirectional"))
      (node (ref "I/O3") (pin "GND2") (pinfunction "4_GND2") (pintype "bidirectional"))
      (node (ref "I/O4") (pin "GND1") (pinfunction "6_GND1") (pintype "bidirectional"))
      (node (ref "I/O4") (pin "GND2") (pinfunction "4_GND2") (pintype "bidirectional"))
      (node (ref "I/O5") (pin "GND1") (pinfunction "6_GND1") (pintype "bidirectional"))
      (node (ref "I/O5") (pin "GND2") (pinfunction "4_GND2") (pintype "bidirectional"))
      (node (ref "I2C") (pin "GND1") (pinfunction "6_GND1") (pintype "bidirectional"))
      (node (ref "I2C") (pin "GND2") (pinfunction "4_GND2") (pintype "bidirectional"))
      (node (ref "IC1") (pin "1") (pinfunction "GND_1") (pintype "power_in"))
      (node (ref "Q1") (pin "3") (pinfunction "S_3") (pintype "passive"))
      (node (ref "Q2") (pin "3") (pinfunction "S_3") (pintype "passive"))
      (node (ref "Q4") (pin "3") (pinfunction "S_3") (pintype "passive"))
      (node (ref "Q5") (pin "3") (pinfunction "S_3") (pintype "passive"))
      (node (ref "Q6") (pin "3") (pinfunction "S_3") (pintype "passive"))
      (node (ref "Q7") (pin "3") (pinfunction "S_3") (pintype "passive"))
      (node (ref "R3") (pin "1") (pinfunction "1_1") (pintype "passive"))
      (node (ref "RESET1") (pin "4") (pinfunction "4_4") (pintype "passive"))
      (node (ref "U$1") (pin "VSS") (pinfunction "GND_VSS") (pintype "bidirectional"))
      (node (ref "U$2") (pin "DGND") (pinfunction "DGND_DGND") (pintype "output"))
      (node (ref "U$2") (pin "GND") (pinfunction "GND_GND") (pintype "power_in"))
      (node (ref "U$3") (pin "GND") (pinfunction "GND_GND") (pintype "bidirectional"))
      (node (ref "U$3") (pin "SND") (pinfunction "SGND_SND") (pintype "bidirectional"))
      (node (ref "U$4") (pin "15") (pinfunction "GND_15") (pintype "bidirectional"))
      (node (ref "U$4") (pin "23") (pinfunction "GND1_23") (pintype "bidirectional"))
      (node (ref "U$4") (pin "5") (pinfunction "UGND_5") (pintype "bidirectional"))
      (node (ref "U$6") (pin "GND1") (pinfunction "GND1_GND1") (pintype "input"))
      (node (ref "U$6") (pin "GND2") (pinfunction "GND2_GND2") (pintype "input"))
      (node (ref "X2") (pin "3") (pinfunction "S_3") (pintype "passive"))
      (node (ref "X4") (pin "5") (pinfunction "5_5") (pintype "passive"))
      (node (ref "X5") (pin "3") (pinfunction "S_3") (pintype "passive"))
    )
    (net (code "41") (name "Net-(3.3V-OK-PadA)") (class "Default")
      (node (ref "3.3V-OK") (pin "A") (pinfunction "A_A") (pintype "passive"))
      (node (ref "R27") (pin "1") (pinfunction "1_1") (pintype "passive"))
    )
    (net (code "42") (name "Net-(5V-OK-PadA)") (class "Default")
      (node (ref "5V-OK") (pin "A") (pinfunction "A_A") (pintype "passive"))
      (node (ref "RL4") (pin "2") (pinfunction "2_2") (pintype "passive"))
    )
    (net (code "43") (name "Net-(12V-OK-PadA)") (class "Default")
      (node (ref "12V-OK") (pin "A") (pinfunction "A_A") (pintype "passive"))
      (node (ref "RL3") (pin "1") (pinfunction "1_1") (pintype "passive"))
    )
    (net (code "44") (name "Net-(BLINK-PadA)") (class "Default")
      (node (ref "BLINK") (pin "A") (pinfunction "A_A") (pintype "passive"))
      (node (ref "RL5") (pin "2") (pinfunction "2_2") (pintype "passive"))
    )
    (net (code "45") (name "Net-(CFG-Pad4)") (class "Default")
      (node (ref "CFG") (pin "4") (pinfunction "4_4") (pintype "passive"))
      (node (ref "U$3") (pin "CFG") (pinfunction "CFG_CFG") (pintype "bidirectional"))
    )
    (net (code "46") (name "Net-(I/O1-2)") (class "Default")
      (node (ref "I/O1") (pin "PWM") (pinfunction "2_PWM") (pintype "bidirectional"))
      (node (ref "LED2") (pin "C") (pinfunction "C_C") (pintype "passive"))
      (node (ref "Q1") (pin "2") (pinfunction "D_2") (pintype "passive"))
    )
    (net (code "47") (name "Net-(I/O1-3)") (class "Default")
      (node (ref "I/O1") (pin "I/O") (pinfunction "3_I/O") (pintype "bidirectional"))
      (node (ref "R") (pin "2") (pinfunction "2_2") (pintype "passive"))
    )
    (net (code "48") (name "Net-(I/O2-2)") (class "Default")
      (node (ref "I/O2") (pin "PWM") (pinfunction "2_PWM") (pintype "bidirectional"))
      (node (ref "LED5") (pin "C") (pinfunction "C_C") (pintype "passive"))
      (node (ref "Q2") (pin "2") (pinfunction "D_2") (pintype "passive"))
    )
    (net (code "49") (name "Net-(I/O2-3)") (class "Default")
      (node (ref "I/O2") (pin "I/O") (pinfunction "3_I/O") (pintype "bidirectional"))
      (node (ref "R32") (pin "2") (pinfunction "2_2") (pintype "passive"))
    )
    (net (code "50") (name "Net-(I/O3-2)") (class "Default")
      (node (ref "I/O3") (pin "PWM") (pinfunction "2_PWM") (pintype "bidirectional"))
      (node (ref "LED6") (pin "C") (pinfunction "C_C") (pintype "passive"))
      (node (ref "Q4") (pin "2") (pinfunction "D_2") (pintype "passive"))
    )
    (net (code "51") (name "Net-(I/O3-3)") (class "Default")
      (node (ref "I/O3") (pin "I/O") (pinfunction "3_I/O") (pintype "bidirectional"))
      (node (ref "R33") (pin "2") (pinfunction "2_2") (pintype "passive"))
    )
    (net (code "52") (name "Net-(I/O4-2)") (class "Default")
      (node (ref "I/O4") (pin "PWM") (pinfunction "2_PWM") (pintype "bidirectional"))
      (node (ref "LED7") (pin "C") (pinfunction "C_C") (pintype "passive"))
      (node (ref "Q5") (pin "2") (pinfunction "D_2") (pintype "passive"))
    )
    (net (code "53") (name "Net-(I/O4-3)") (class "Default")
      (node (ref "I/O4") (pin "I/O") (pinfunction "3_I/O") (pintype "bidirectional"))
      (node (ref "R34") (pin "2") (pinfunction "2_2") (pintype "passive"))
    )
    (net (code "54") (name "Net-(I/O5-2)") (class "Default")
      (node (ref "I/O5") (pin "PWM") (pinfunction "2_PWM") (pintype "bidirectional"))
      (node (ref "LED8") (pin "C") (pinfunction "C_C") (pintype "passive"))
      (node (ref "Q6") (pin "2") (pinfunction "D_2") (pintype "passive"))
    )
    (net (code "55") (name "Net-(I/O5-3)") (class "Default")
      (node (ref "I/O5") (pin "I/O") (pinfunction "3_I/O") (pintype "bidirectional"))
      (node (ref "R35") (pin "2") (pinfunction "2_2") (pintype "passive"))
    )
    (net (code "56") (name "Net-(IC2-+)") (class "Default")
      (node (ref "C13") (pin "1") (pinfunction "1_1") (pintype "passive"))
      (node (ref "C14") (pin "2") (pinfunction "2_2") (pintype "passive"))
      (node (ref "IC2") (pin "3") (pinfunction "+_3") (pintype "input"))
      (node (ref "R19") (pin "1") (pinfunction "1_1") (pintype "passive"))
    )
    (net (code "57") (name "Net-(IC2--)") (class "Default")
      (node (ref "C13") (pin "2") (pinfunction "2_2") (pintype "passive"))
      (node (ref "C15") (pin "1") (pinfunction "1_1") (pintype "passive"))
      (node (ref "IC2") (pin "2") (pinfunction "-_2") (pintype "input"))
      (node (ref "R20") (pin "1") (pinfunction "1_1") (pintype "passive"))
    )
    (net (code "58") (name "Net-(IC2-OUT)") (class "Default")
      (node (ref "IC2") (pin "6") (pinfunction "OUT_6") (pintype "output"))
      (node (ref "R9") (pin "1") (pinfunction "1_1") (pintype "passive"))
    )
    (net (code "59") (name "Net-(IC2-RG-Pad1)") (class "Default")
      (node (ref "IC2") (pin "1") (pinfunction "RG_1") (pintype "passive"))
      (node (ref "R2") (pin "2") (pinfunction "2_2") (pintype "passive"))
    )
    (net (code "60") (name "Net-(IC2-RG-Pad8)") (class "Default")
      (node (ref "IC2") (pin "8") (pinfunction "RG_8") (pintype "passive"))
      (node (ref "R2") (pin "1") (pinfunction "1_1") (pintype "passive"))
    )
    (net (code "61") (name "Net-(J7B-S)") (class "Default")
      (node (ref "J7") (pin "2") (pinfunction "S_2") (pintype "passive"))
      (node (ref "Q7") (pin "2") (pinfunction "D_2") (pintype "passive"))
    )
    (net (code "62") (name "Net-(LED2-PadA)") (class "Default")
      (node (ref "LED2") (pin "A") (pinfunction "A_A") (pintype "passive"))
      (node (ref "R25") (pin "1") (pinfunction "1_1") (pintype "passive"))
    )
    (net (code "63") (name "Net-(LED5-PadA)") (class "Default")
      (node (ref "LED5") (pin "A") (pinfunction "A_A") (pintype "passive"))
      (node (ref "R4") (pin "1") (pinfunction "1_1") (pintype "passive"))
    )
    (net (code "64") (name "Net-(LED6-PadA)") (class "Default")
      (node (ref "LED6") (pin "A") (pinfunction "A_A") (pintype "passive"))
      (node (ref "R5") (pin "1") (pinfunction "1_1") (pintype "passive"))
    )
    (net (code "65") (name "Net-(LED7-PadA)") (class "Default")
      (node (ref "LED7") (pin "A") (pinfunction "A_A") (pintype "passive"))
      (node (ref "R6") (pin "1") (pinfunction "1_1") (pintype "passive"))
    )
    (net (code "66") (name "Net-(LED8-PadA)") (class "Default")
      (node (ref "LED8") (pin "A") (pinfunction "A_A") (pintype "passive"))
      (node (ref "R7") (pin "1") (pinfunction "1_1") (pintype "passive"))
    )
    (net (code "67") (name "Net-(LED9-PadA)") (class "Default")
      (node (ref "LED9") (pin "A") (pinfunction "A_A") (pintype "passive"))
      (node (ref "R12") (pin "1") (pinfunction "1_1") (pintype "passive"))
    )
    (net (code "68") (name "Net-(LED11-PadA)") (class "Default")
      (node (ref "LED11") (pin "A") (pinfunction "A_A") (pintype "passive"))
      (node (ref "R14") (pin "1") (pinfunction "1_1") (pintype "passive"))
    )
    (net (code "69") (name "Net-(LED11-PadC)") (class "Default")
      (node (ref "LED11") (pin "C") (pinfunction "C_C") (pintype "passive"))
      (node (ref "U$3") (pin "NET") (pinfunction "NET_NET") (pintype "bidirectional"))
    )
    (net (code "70") (name "Net-(LED12-PadA)") (class "Default")
      (node (ref "LED12") (pin "A") (pinfunction "A_A") (pintype "passive"))
      (node (ref "R39") (pin "1") (pinfunction "1_1") (pintype "passive"))
    )
    (net (code "71") (name "Net-(LED12-PadC)") (class "Default")
      (node (ref "LED12") (pin "C") (pinfunction "C_C") (pintype "passive"))
      (node (ref "U$3") (pin "ALM") (pinfunction "ALM_ALM") (pintype "bidirectional"))
    )
    (net (code "72") (name "Net-(Q7-G)") (class "Default")
      (node (ref "Q7") (pin "1") (pinfunction "G_1") (pintype "passive"))
      (node (ref "RL2") (pin "2") (pinfunction "2_2") (pintype "passive"))
    )
    (net (code "73") (name "Net-(R8-Pad2)") (class "Default")
      (node (ref "R8") (pin "2") (pinfunction "2_2") (pintype "passive"))
      (node (ref "U$3") (pin "TX1") (pinfunction "TX1_TX1") (pintype "bidirectional"))
    )
    (net (code "74") (name "Net-(R11-Pad2)") (class "Default")
      (node (ref "R11") (pin "2") (pinfunction "2_2") (pintype "passive"))
      (node (ref "U$3") (pin "RX1") (pinfunction "RX1_RX1") (pintype "bidirectional"))
    )
    (net (code "75") (name "Net-(R18-Pad2)") (class "Default")
      (node (ref "R18") (pin "2") (pinfunction "2_2") (pintype "passive"))
      (node (ref "U$1") (pin "SCK") (pinfunction "SCK_SCK") (pintype "bidirectional"))
    )
    (net (code "76") (name "Net-(R24-Pad2)") (class "Default")
      (node (ref "R24") (pin "2") (pinfunction "2_2") (pintype "passive"))
      (node (ref "X4") (pin "3") (pinfunction "3_3") (pintype "passive"))
    )
    (net (code "77") (name "Net-(R31-Pad2)") (class "Default")
      (node (ref "R31") (pin "2") (pinfunction "2_2") (pintype "passive"))
      (node (ref "X4") (pin "2") (pinfunction "2_2") (pintype "passive"))
    )
    (net (code "78") (name "Net-(U$1-CS)") (class "Default")
      (node (ref "R16") (pin "1") (pinfunction "1_1") (pintype "passive"))
      (node (ref "R17") (pin "1") (pinfunction "1_1") (pintype "passive"))
      (node (ref "U$1") (pin "CE") (pinfunction "CS_CE") (pintype "bidirectional"))
    )
    (net (code "79") (name "Net-(U$3-RNU)") (class "Default")
      (node (ref "LED9") (pin "C") (pinfunction "C_C") (pintype "passive"))
      (node (ref "U$3") (pin "RUN") (pinfunction "RNU_RUN") (pintype "bidirectional"))
    )
    (net (code "80") (name "Net-(U$4-AVCC)") (class "Default")
      (node (ref "C16") (pin "2") (pinfunction "2_2") (pintype "passive"))
      (node (ref "L1") (pin "1") (pinfunction "1_1") (pintype "passive"))
      (node (ref "U$4") (pin "24") (pinfunction "AVCC_24") (pintype "bidirectional"))
    )
    (net (code "81") (name "Net-(U$4-UCAP)") (class "Default")
      (node (ref "C3") (pin "2") (pinfunction "2_2") (pintype "passive"))
      (node (ref "U$4") (pin "6") (pinfunction "UCAP_6") (pintype "bidirectional"))
    )
    (net (code "82") (name "Net-(X1B-S)") (class "Default")
      (node (ref "R20") (pin "2") (pinfunction "2_2") (pintype "passive"))
      (node (ref "X1") (pin "2") (pinfunction "S_2") (pintype "passive"))
    )
    (net (code "83") (name "Net-(X1C-S)") (class "Default")
      (node (ref "R19") (pin "2") (pinfunction "2_2") (pintype "passive"))
      (node (ref "X1") (pin "3") (pinfunction "S_3") (pintype "passive"))
    )
    (net (code "84") (name "Net-(X2B-S)") (class "Default")
      (node (ref "R10") (pin "2") (pinfunction "2_2") (pintype "passive"))
      (node (ref "RL6") (pin "2") (pinfunction "2_2") (pintype "passive"))
      (node (ref "X2") (pin "2") (pinfunction "S_2") (pintype "passive"))
    )
    (net (code "85") (name "Net-(X5B-S)") (class "Default")
      (node (ref "R21") (pin "2") (pinfunction "2_2") (pintype "passive"))
      (node (ref "RL8") (pin "2") (pinfunction "2_2") (pintype "passive"))
      (node (ref "X5") (pin "2") (pinfunction "S_2") (pintype "passive"))
    )
    (net (code "86") (name "VUSB") (class "Default")
      (node (ref "C7") (pin "2") (pinfunction "2_2") (pintype "passive"))
      (node (ref "D4") (pin "A") (pinfunction "A_A") (pintype "passive"))
      (node (ref "U$4") (pin "7") (pinfunction "VBUS_7") (pintype "bidirectional"))
      (node (ref "X4") (pin "1") (pinfunction "1_1") (pintype "passive"))
    )
    (net (code "87") (name "unconnected-(CFG-Pad2)") (class "Default")
      (node (ref "CFG") (pin "2") (pinfunction "2_2") (pintype "passive"))
    )
    (net (code "88") (name "unconnected-(CFG-Pad3)") (class "Default")
      (node (ref "CFG") (pin "3") (pinfunction "3_3") (pintype "passive"))
    )
    (net (code "89") (name "unconnected-(Q1-D-Pad4)") (class "Default")
      (node (ref "Q1") (pin "4") (pinfunction "D_4") (pintype "passive"))
    )
    (net (code "90") (name "unconnected-(Q2-D-Pad4)") (class "Default")
      (node (ref "Q2") (pin "4") (pinfunction "D_4") (pintype "passive"))
    )
    (net (code "91") (name "unconnected-(Q4-D-Pad4)") (class "Default")
      (node (ref "Q4") (pin "4") (pinfunction "D_4") (pintype "passive"))
    )
    (net (code "92") (name "unconnected-(Q5-D-Pad4)") (class "Default")
      (node (ref "Q5") (pin "4") (pinfunction "D_4") (pintype "passive"))
    )
    (net (code "93") (name "unconnected-(Q6-D-Pad4)") (class "Default")
      (node (ref "Q6") (pin "4") (pinfunction "D_4") (pintype "passive"))
    )
    (net (code "94") (name "unconnected-(RESET1-Pad1)") (class "Default")
      (node (ref "RESET1") (pin "1") (pinfunction "1_1") (pintype "passive"))
    )
    (net (code "95") (name "unconnected-(RESET1-Pad3)") (class "Default")
      (node (ref "RESET1") (pin "3") (pinfunction "3_3") (pintype "passive"))
    )
    (net (code "96") (name "unconnected-(U$3-PadRST)") (class "Default")
      (node (ref "U$3") (pin "RST") (pinfunction "RST_RST") (pintype "bidirectional"))
    )
    (net (code "97") (name "unconnected-(X4-Pad4)") (class "Default")
      (node (ref "X4") (pin "4") (pinfunction "4_4") (pintype "passive"))
    )
  )
)
